# LP38693_5V_LDO_breakout.net
KiCad netlist of a schematic drawn in EAGLE
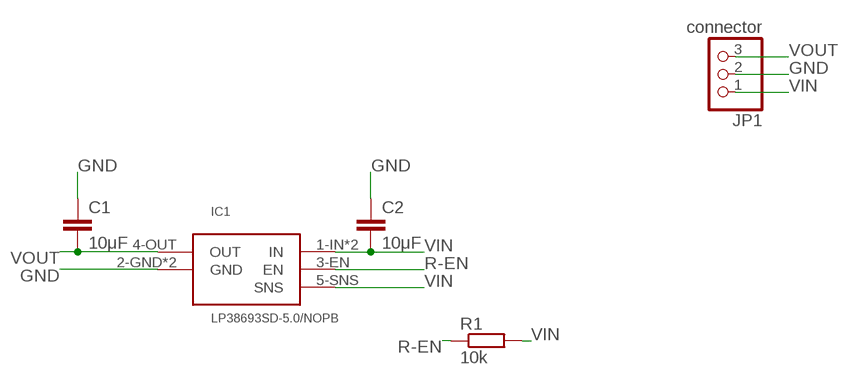
[diagram p0: schematic, sheet 1]

(export (version "E")
  (design (tool "Eeschema 10.0.6"))
  (components
    (comp (ref "C1")
      (value "10μF")
      (footprint "eagle-import:C0402")
      (libsource (lib "eagle-import") (part "C-EUC0402"))
    )
    (comp (ref "C2")
      (value "10μF")
      (footprint "eagle-import:C0402")
      (libsource (lib "eagle-import") (part "C-EUC0402"))
    )
    (comp (ref "IC1")
      (value "LP38693SD-5.0/NOPB")
      (footprint "eagle-import:WSON6")
      (libsource (lib "eagle-import") (part "LP38693"))
    )
    (comp (ref "JP1")
      (value "connector")
      (footprint "eagle-import:1X03")
      (libsource (lib "eagle-import") (part "PINHD-1X3"))
    )
    (comp (ref "R1")
      (value "10k")
      (footprint "eagle-import:R0402")
      (libsource (lib "eagle-import") (part "R-EU_R0402"))
    )
  )
  (nets
    (net (code "1") (name "/GND") (class "Default")
      (node (ref "C1") (pin "1") (pinfunction "1_1") (pintype "passive"))
      (node (ref "C2") (pin "1") (pinfunction "1_1") (pintype "passive"))
      (node (ref "IC1") (pin "2-GND") (pinfunction "GND_2-GND") (pintype "bidirectional"))
      (node (ref "IC1") (pin "GND1") (pinfunction "GND_GND1") (pintype "bidirectional"))
      (node (ref "JP1") (pin "2") (pinfunction "2_2") (pintype "passive"))
    )
    (net (code "2") (name "/R-EN") (class "Default")
      (node (ref "IC1") (pin "3-EN") (pinfunction "EN_3-EN") (pintype "bidirectional"))
      (node (ref "R1") (pin "1") (pinfunction "1_1") (pintype "passive"))
    )
    (net (code "3") (name "/VIN") (class "Default")
      (node (ref "C2") (pin "2") (pinfunction "2_2") (pintype "passive"))
      (node (ref "IC1") (pin "1-IN") (pinfunction "IN_1-IN") (pintype "bidirectional"))
      (node (ref "IC1") (pin "5-SNS") (pinfunction "SNS_5-SNS") (pintype "bidirectional"))
      (node (ref "IC1") (pin "6-IN") (pinfunction "IN_6-IN") (pintype "bidirectional"))
      (node (ref "JP1") (pin "1") (pinfunction "1_1") (pintype "passive"))
      (node (ref "R1") (pin "2") (pinfunction "2_2") (pintype "passive"))
    )
    (net (code "4") (name "/VOUT") (class "Default")
      (node (ref "C1") (pin "2") (pinfunction "2_2") (pintype "passive"))
      (node (ref "IC1") (pin "4-OUT") (pinfunction "OUT_4-OUT") (pintype "bidirectional"))
      (node (ref "JP1") (pin "3") (pinfunction "3_3") (pintype "passive"))
    )
  )
)
